# OPNpool_r3.net
KiCad netlist of a schematic drawn in EAGLE
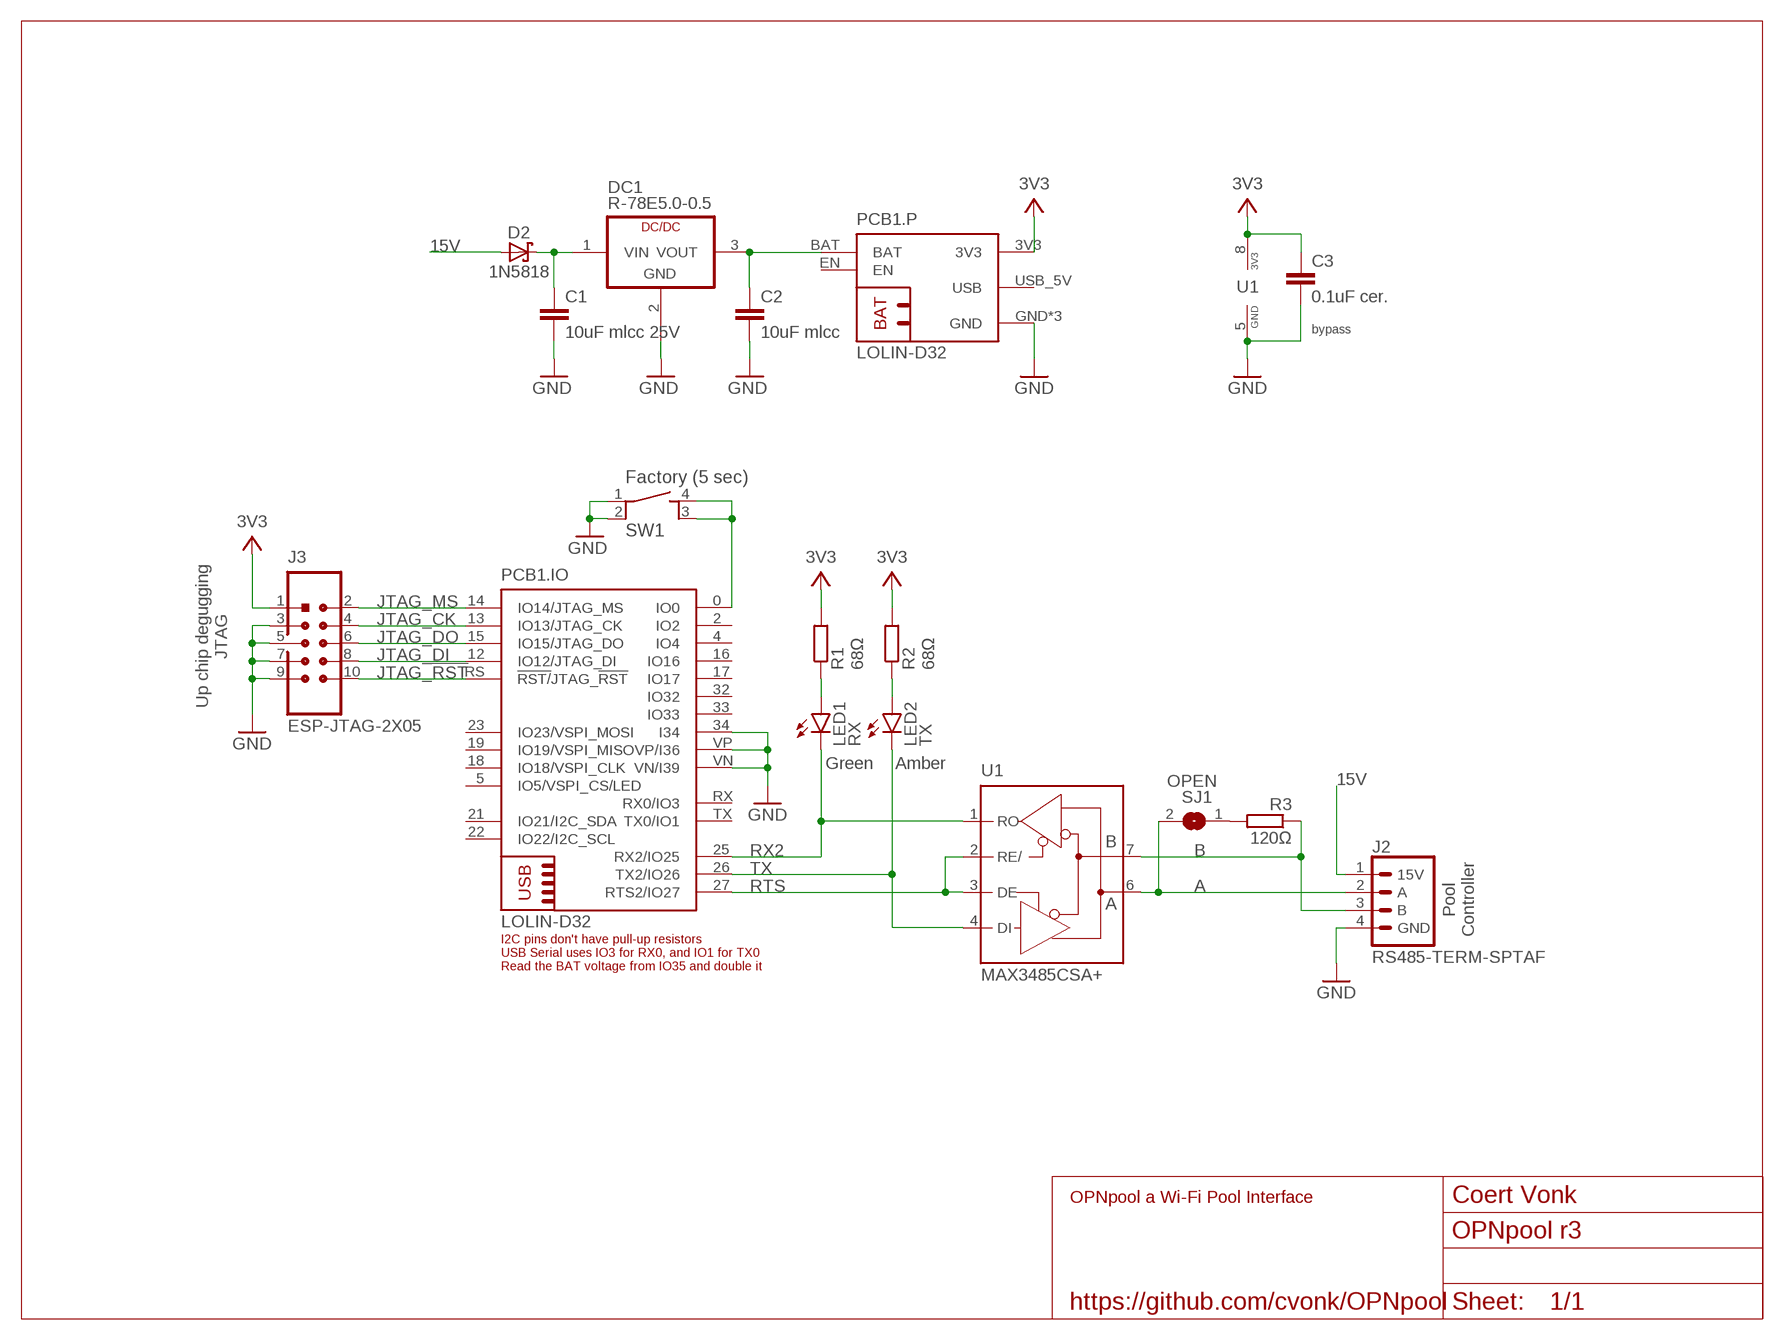
[diagram p0: schematic, sheet 1]

(export (version "E")
  (design (tool "Eeschema 10.0.6"))
  (components
    (comp (ref "C1")
      (value "10uF mlcc 25V")
      (footprint "eagle-import:C0805K")
      (fields (field (name "MANF") "Murata Electronics"))
      (libsource (lib "eagle-import") (part "C-EUC0805K"))
    )
    (comp (ref "C2")
      (value "10uF mlcc")
      (footprint "eagle-import:C0805K")
      (fields (field (name "MANF") "Murata Electronics"))
      (libsource (lib "eagle-import") (part "C-EUC0805K"))
    )
    (comp (ref "C3")
      (value "0.1uF cer.")
      (footprint "eagle-import:C0805K")
      (fields (field (name "MANF") "KEMET"))
      (libsource (lib "eagle-import") (part "C-EUC0805K"))
    )
    (comp (ref "D2")
      (value "1N5818")
      (footprint "eagle-import:DO41-7.6")
      (fields (field (name "MANF") "Rectron"))
      (libsource (lib "eagle-import") (part "1N5818"))
    )
    (comp (ref "DC1")
      (value "R-78E5.0-0.5")
      (footprint "eagle-import:SIP3")
      (fields (field (name "MANF") "RECOM Power"))
      (libsource (lib "eagle-import") (part "R-78E-0.55.0"))
    )
    (comp (ref "J2")
      (value "RS485-TERM-SPTAF")
      (footprint "eagle-import:SPTAF1_4-5,0-LL")
      (fields (field (name "MANF") "Phoenix Contact"))
      (libsource (lib "eagle-import") (part "RS485-TERM-SPTAF"))
    )
    (comp (ref "J3")
      (value "ESP-JTAG-2X05")
      (footprint "eagle-import:2X05_SHROUDED")
      (fields (field (name "MANF") "Molex"))
      (libsource (lib "eagle-import") (part "ESP-JTAG-2X05"))
    )
    (comp (ref "LED1")
      (value "RX")
      (footprint "eagle-import:CHIPLED_0805")
      (libsource (lib "eagle-import") (part "LEDCHIPLED_0805"))
    )
    (comp (ref "LED2")
      (value "TX")
      (footprint "eagle-import:CHIPLED_0805")
      (libsource (lib "eagle-import") (part "LEDCHIPLED_0805"))
    )
    (comp (ref "PCB1")
      (value "LOLIN-D32")
      (footprint "eagle-import:LOLIN-D32")
      (libsource (lib "eagle-import") (part "LOLIN-D32"))
    )
    (comp (ref "R1")
      (value "68Ω")
      (footprint "eagle-import:R0805")
      (fields (field (name "MANF") "Bourns"))
      (libsource (lib "eagle-import") (part "R-EU_R0805"))
    )
    (comp (ref "R2")
      (value "68Ω")
      (footprint "eagle-import:R0805")
      (fields (field (name "MANF") "Bourns"))
      (libsource (lib "eagle-import") (part "R-EU_R0805"))
    )
    (comp (ref "R3")
      (value "120Ω")
      (footprint "eagle-import:R0805")
      (fields (field (name "MANF") "Bourns"))
      (libsource (lib "eagle-import") (part "R-EU_R0805"))
    )
    (comp (ref "SJ1")
      (value "OPEN")
      (footprint "eagle-import:SJ")
      (libsource (lib "eagle-import") (part "SJ"))
    )
    (comp (ref "SW1")
      (value "Factory (5 sec)")
      (footprint "eagle-import:TE_1-1825910-4")
      (fields
        (field (name "COMMENT") "1-1825910-4")
        (field (name "DIGI-KEY_PART_NUMBER") "450-1653-ND")
        (field (name "MF") "TE Connectivity")
      )
      (libsource (lib "eagle-import") (part "1-1825910-4"))
    )
    (comp (ref "U1")
      (value "MAX3485CSA+")
      (footprint "eagle-import:SO08")
      (fields
        (field (name "MF") "MAXIM")
        (field (name "MPN") "MAX481CSA")
        (field (name "MANF") "Maxim Integrated")
        (field (name "MANF#") "MAX3485CSA+")
        (field (name "MOUSER#") "700-MAX3485CSA")
      )
      (libsource (lib "eagle-import") (part "MAX3485CSA+"))
    )
  )
  (nets
    (net (code "1") (name "/15V") (class "Default")
      (node (ref "D2") (pin "A") (pinfunction "A_A") (pintype "passive"))
      (node (ref "J2") (pin "1") (pinfunction "15V_1") (pintype "power_in"))
    )
    (net (code "2") (name "/A") (class "Default")
      (node (ref "J2") (pin "2") (pinfunction "A_2") (pintype "passive"))
      (node (ref "SJ1") (pin "2") (pinfunction "2_2") (pintype "passive"))
      (node (ref "U1") (pin "6") (pinfunction "A_6") (pintype "passive"))
    )
    (net (code "3") (name "/B") (class "Default")
      (node (ref "J2") (pin "3") (pinfunction "B_3") (pintype "passive"))
      (node (ref "R3") (pin "1") (pinfunction "1_1") (pintype "passive"))
      (node (ref "U1") (pin "7") (pinfunction "B_7") (pintype "passive"))
    )
    (net (code "4") (name "/JTAG_CK") (class "Default")
      (node (ref "J3") (pin "4") (pinfunction "TCK_4") (pintype "passive"))
      (node (ref "PCB1") (pin "13") (pinfunction "IO13/JTAG_CK_13") (pintype "bidirectional"))
    )
    (net (code "5") (name "/JTAG_DI") (class "Default")
      (node (ref "J3") (pin "8") (pinfunction "TDI_8") (pintype "passive"))
      (node (ref "PCB1") (pin "12") (pinfunction "IO12/JTAG_DI_12") (pintype "bidirectional"))
    )
    (net (code "6") (name "/JTAG_DO") (class "Default")
      (node (ref "J3") (pin "6") (pinfunction "TDO_6") (pintype "passive"))
      (node (ref "PCB1") (pin "15") (pinfunction "IO15/JTAG_DO_15") (pintype "bidirectional"))
    )
    (net (code "7") (name "/JTAG_MS") (class "Default")
      (node (ref "J3") (pin "2") (pinfunction "TMS_2") (pintype "passive"))
      (node (ref "PCB1") (pin "14") (pinfunction "IO14/JTAG_MS_14") (pintype "bidirectional"))
    )
    (net (code "8") (name "/JTAG_~{RST}") (class "Default")
      (node (ref "J3") (pin "10") (pinfunction "NC_10") (pintype "passive"))
      (node (ref "PCB1") (pin "RS") (pinfunction "~{RST/}JTAG_~{RST}_RS") (pintype "input"))
    )
    (net (code "9") (name "/RTS") (class "Default")
      (node (ref "PCB1") (pin "27") (pinfunction "RTS2/IO27_27") (pintype "bidirectional"))
      (node (ref "U1") (pin "2") (pinfunction "RE/_2") (pintype "input"))
      (node (ref "U1") (pin "3") (pinfunction "DE_3") (pintype "input"))
    )
    (net (code "10") (name "/RX2") (class "Default")
      (node (ref "LED1") (pin "C") (pinfunction "C_C") (pintype "passive"))
      (node (ref "PCB1") (pin "25") (pinfunction "RX2/IO25_25") (pintype "bidirectional"))
      (node (ref "U1") (pin "1") (pinfunction "RO_1") (pintype "output"))
    )
    (net (code "11") (name "/TX") (class "Default")
      (node (ref "LED2") (pin "C") (pinfunction "C_C") (pintype "passive"))
      (node (ref "PCB1") (pin "26") (pinfunction "TX2/IO26_26") (pintype "bidirectional"))
      (node (ref "U1") (pin "4") (pinfunction "DI_4") (pintype "input"))
    )
    (net (code "12") (name "/USB") (class "Default")
      (node (ref "PCB1") (pin "USB_5V") (pinfunction "USB_USB_5V") (pintype "power_in"))
    )
    (net (code "13") (name "3V3") (class "Default")
      (node (ref "C3") (pin "1") (pinfunction "1_1") (pintype "passive"))
      (node (ref "J3") (pin "1") (pinfunction "3V3_1") (pintype "power_in"))
      (node (ref "PCB1") (pin "3V3") (pinfunction "3V3_3V3") (pintype "power_in"))
      (node (ref "R1") (pin "2") (pinfunction "2_2") (pintype "passive"))
      (node (ref "R2") (pin "2") (pinfunction "2_2") (pintype "passive"))
      (node (ref "U1") (pin "8") (pinfunction "VCC_8") (pintype "passive"))
    )
    (net (code "14") (name "GND") (class "Default")
      (node (ref "C1") (pin "2") (pinfunction "2_2") (pintype "passive"))
      (node (ref "C2") (pin "2") (pinfunction "2_2") (pintype "passive"))
      (node (ref "C3") (pin "2") (pinfunction "2_2") (pintype "passive"))
      (node (ref "DC1") (pin "2") (pinfunction "GND_2") (pintype "power_in"))
      (node (ref "J2") (pin "4") (pinfunction "GND_4") (pintype "power_in"))
      (node (ref "J3") (pin "3") (pinfunction "GND_3") (pintype "power_in"))
      (node (ref "J3") (pin "5") (pinfunction "GND_5") (pintype "power_in"))
      (node (ref "J3") (pin "7") (pinfunction "GND_7") (pintype "power_in"))
      (node (ref "J3") (pin "9") (pinfunction "GND_9") (pintype "power_in"))
      (node (ref "PCB1") (pin "34") (pinfunction "I34_34") (pintype "input"))
      (node (ref "PCB1") (pin "GND") (pinfunction "GND_GND") (pintype "power_in"))
      (node (ref "PCB1") (pin "GND@1") (pinfunction "GND_GND@1") (pintype "power_in"))
      (node (ref "PCB1") (pin "GND@2") (pinfunction "GND_GND@2") (pintype "power_in"))
      (node (ref "PCB1") (pin "VN") (pinfunction "VN/I39_VN") (pintype "input"))
      (node (ref "PCB1") (pin "VP") (pinfunction "VP/I36_VP") (pintype "input"))
      (node (ref "SW1") (pin "1") (pinfunction "1_1") (pintype "passive"))
      (node (ref "SW1") (pin "2") (pinfunction "2_2") (pintype "passive"))
      (node (ref "U1") (pin "5") (pinfunction "GND_5") (pintype "power_in"))
    )
    (net (code "15") (name "Net-(DC1-VIN)") (class "Default")
      (node (ref "C1") (pin "1") (pinfunction "1_1") (pintype "passive"))
      (node (ref "D2") (pin "C") (pinfunction "C_C") (pintype "passive"))
      (node (ref "DC1") (pin "1") (pinfunction "VIN_1") (pintype "power_in"))
    )
    (net (code "16") (name "Net-(DC1-VOUT)") (class "Default")
      (node (ref "C2") (pin "1") (pinfunction "1_1") (pintype "passive"))
      (node (ref "DC1") (pin "3") (pinfunction "VOUT_3") (pintype "power_in"))
      (node (ref "PCB1") (pin "BAT") (pinfunction "BAT_BAT") (pintype "power_in"))
    )
    (net (code "17") (name "Net-(LED1-PadA)") (class "Default")
      (node (ref "LED1") (pin "A") (pinfunction "A_A") (pintype "passive"))
      (node (ref "R1") (pin "1") (pinfunction "1_1") (pintype "passive"))
    )
    (net (code "18") (name "Net-(LED2-PadA)") (class "Default")
      (node (ref "LED2") (pin "A") (pinfunction "A_A") (pintype "passive"))
      (node (ref "R2") (pin "1") (pinfunction "1_1") (pintype "passive"))
    )
    (net (code "19") (name "Net-(PCB1A-IO0)") (class "Default")
      (node (ref "PCB1") (pin "0") (pinfunction "IO0_0") (pintype "bidirectional"))
      (node (ref "SW1") (pin "3") (pinfunction "3_3") (pintype "passive"))
      (node (ref "SW1") (pin "4") (pinfunction "4_4") (pintype "passive"))
    )
    (net (code "20") (name "Net-(R3-Pad2)") (class "Default")
      (node (ref "R3") (pin "2") (pinfunction "2_2") (pintype "passive"))
      (node (ref "SJ1") (pin "1") (pinfunction "1_1") (pintype "passive"))
    )
    (net (code "21") (name "unconnected-(PCB1-PadEN)") (class "Default")
      (node (ref "PCB1") (pin "EN") (pinfunction "EN_EN") (pintype "passive"))
    )
    (net (code "22") (name "unconnected-(PCB1A-IO2-Pad2)") (class "Default")
      (node (ref "PCB1") (pin "2") (pinfunction "IO2_2") (pintype "bidirectional"))
    )
    (net (code "23") (name "unconnected-(PCB1A-IO4-Pad4)") (class "Default")
      (node (ref "PCB1") (pin "4") (pinfunction "IO4_4") (pintype "bidirectional"))
    )
    (net (code "24") (name "unconnected-(PCB1A-IO5{slash}VSPI_CS{slash}LED-Pad5)") (class "Default")
      (node (ref "PCB1") (pin "5") (pinfunction "IO5/VSPI_CS/LED_5") (pintype "bidirectional"))
    )
    (net (code "25") (name "unconnected-(PCB1A-IO16-Pad16)") (class "Default")
      (node (ref "PCB1") (pin "16") (pinfunction "IO16_16") (pintype "bidirectional"))
    )
    (net (code "26") (name "unconnected-(PCB1A-IO17-Pad17)") (class "Default")
      (node (ref "PCB1") (pin "17") (pinfunction "IO17_17") (pintype "bidirectional"))
    )
    (net (code "27") (name "unconnected-(PCB1A-IO18{slash}VSPI_CLK-Pad18)") (class "Default")
      (node (ref "PCB1") (pin "18") (pinfunction "IO18/VSPI_CLK_18") (pintype "bidirectional"))
    )
    (net (code "28") (name "unconnected-(PCB1A-IO19{slash}VSPI_MISO-Pad19)") (class "Default")
      (node (ref "PCB1") (pin "19") (pinfunction "IO19/VSPI_MISO_19") (pintype "bidirectional"))
    )
    (net (code "29") (name "unconnected-(PCB1A-IO21{slash}I2C_SDA-Pad21)") (class "Default")
      (node (ref "PCB1") (pin "21") (pinfunction "IO21/I2C_SDA_21") (pintype "bidirectional"))
    )
    (net (code "30") (name "unconnected-(PCB1A-IO22{slash}I2C_SCL-Pad22)") (class "Default")
      (node (ref "PCB1") (pin "22") (pinfunction "IO22/I2C_SCL_22") (pintype "bidirectional"))
    )
    (net (code "31") (name "unconnected-(PCB1A-IO23{slash}VSPI_MOSI-Pad23)") (class "Default")
      (node (ref "PCB1") (pin "23") (pinfunction "IO23/VSPI_MOSI_23") (pintype "bidirectional"))
    )
    (net (code "32") (name "unconnected-(PCB1A-IO32-Pad32)") (class "Default")
      (node (ref "PCB1") (pin "32") (pinfunction "IO32_32") (pintype "bidirectional"))
    )
    (net (code "33") (name "unconnected-(PCB1A-IO33-Pad33)") (class "Default")
      (node (ref "PCB1") (pin "33") (pinfunction "IO33_33") (pintype "bidirectional"))
    )
    (net (code "34") (name "unconnected-(PCB1A-RX0{slash}IO3-PadRX)") (class "Default")
      (node (ref "PCB1") (pin "RX") (pinfunction "RX0/IO3_RX") (pintype "bidirectional"))
    )
    (net (code "35") (name "unconnected-(PCB1A-TX0{slash}IO1-PadTX)") (class "Default")
      (node (ref "PCB1") (pin "TX") (pinfunction "TX0/IO1_TX") (pintype "bidirectional"))
    )
  )
)
